# Sheet1.net
KiCad netlist of a schematic drawn in Altium Designer
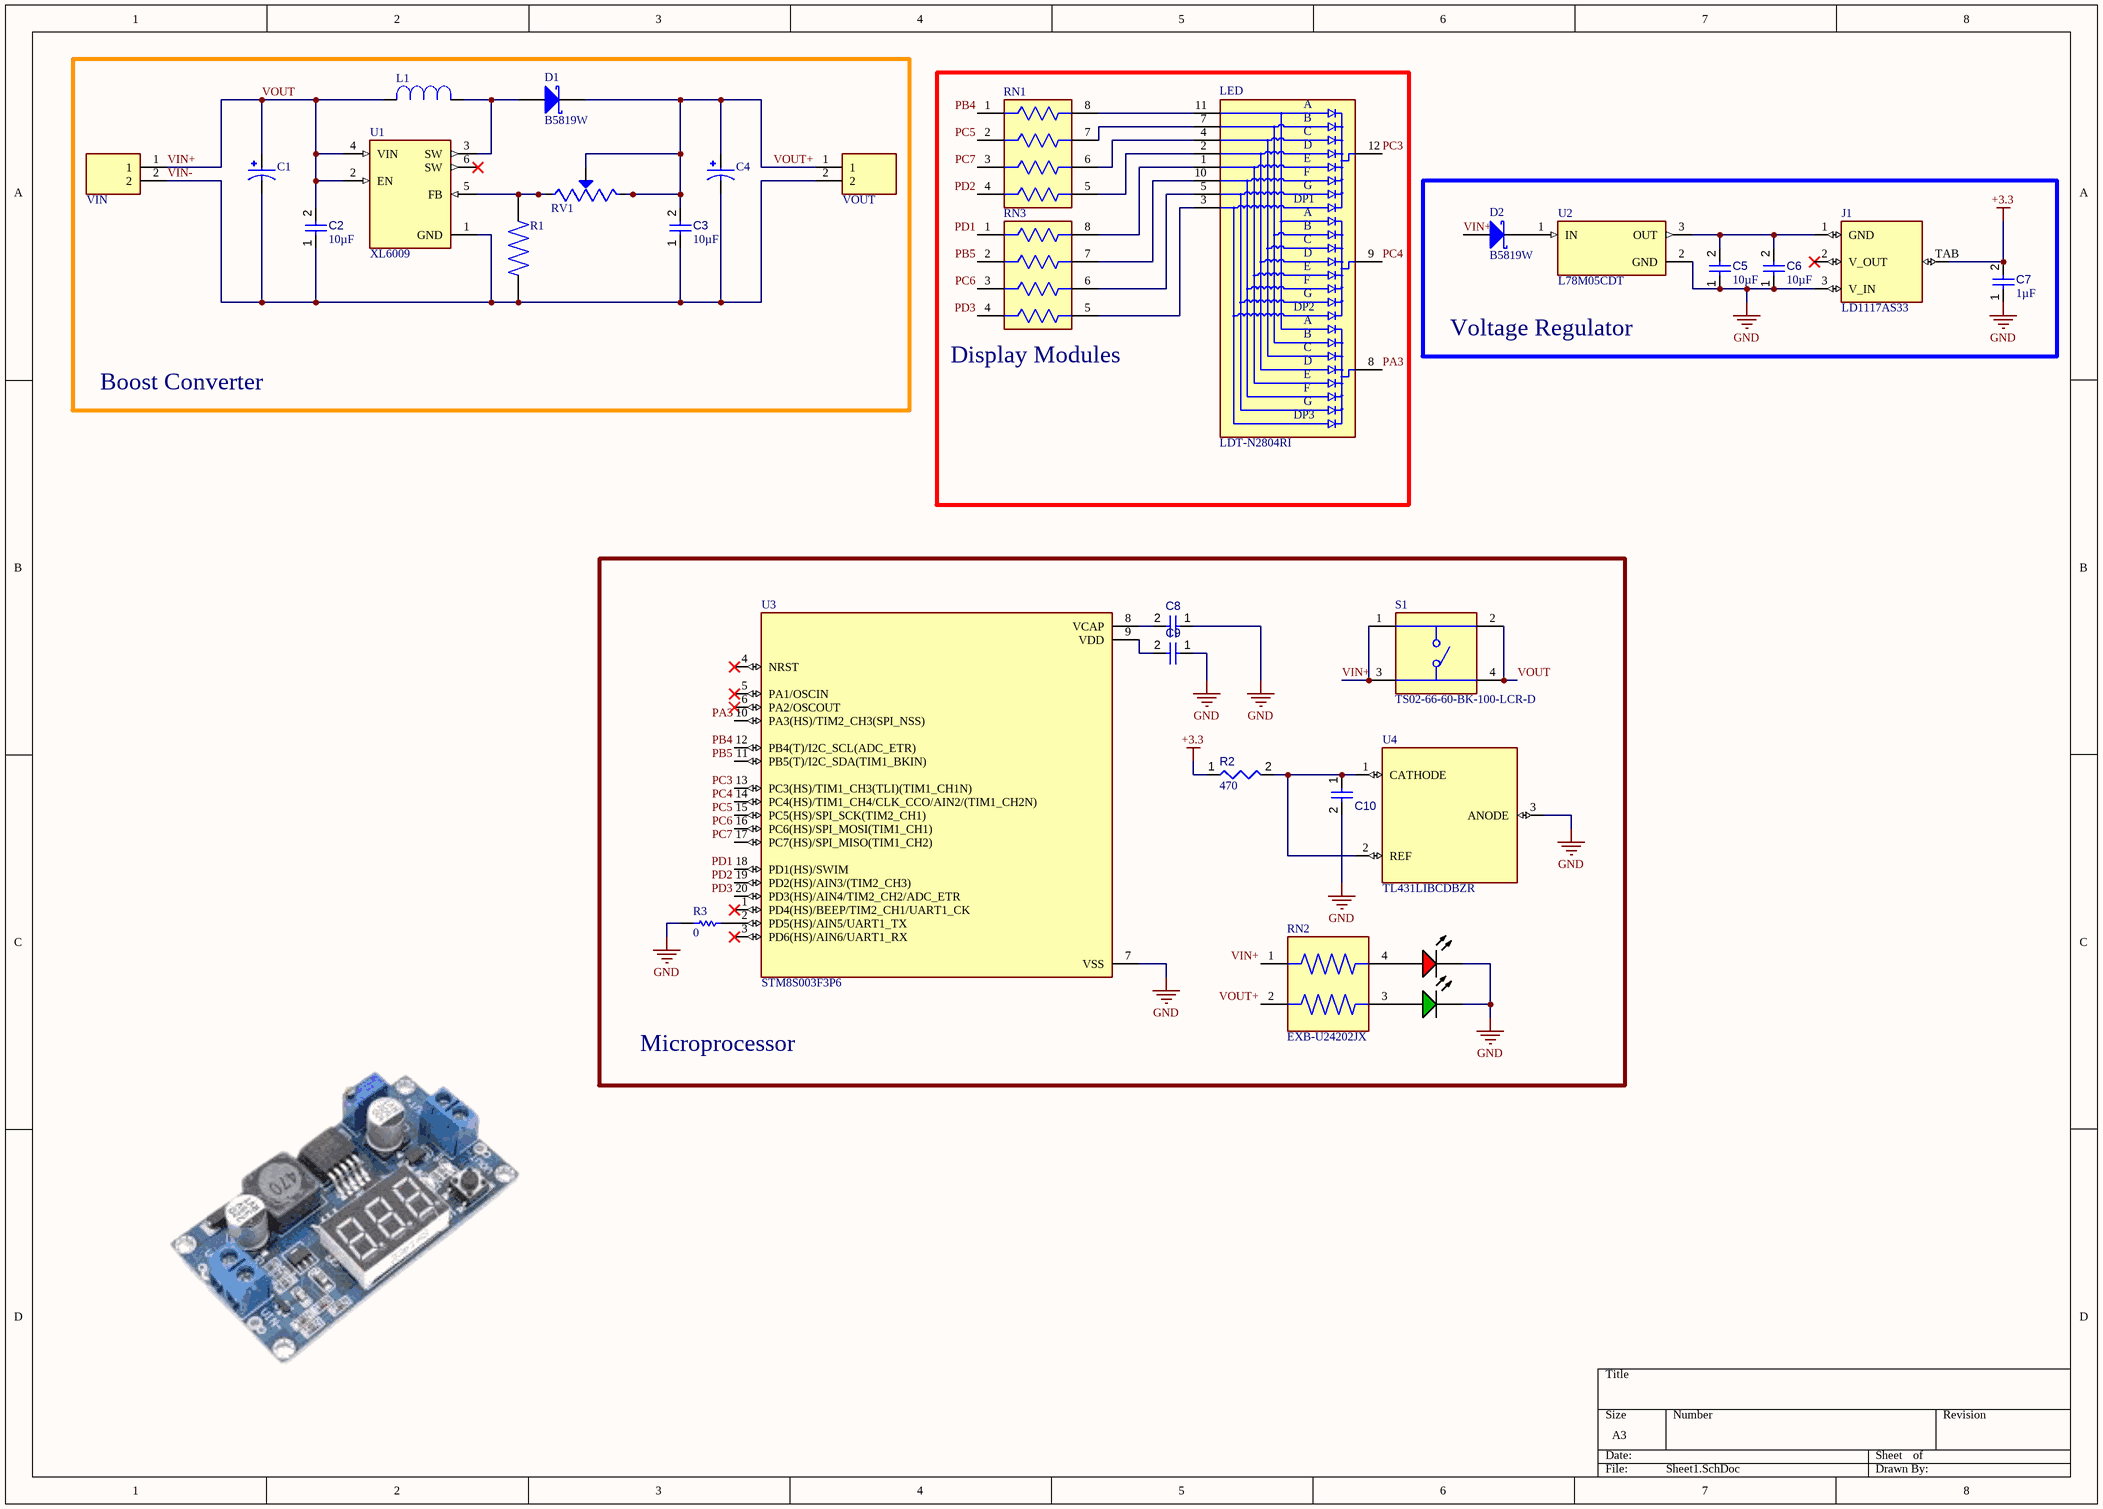
[diagram p0: Sheet1.SchDoc]

(export (version "E")
  (design (tool "Eeschema 10.0.6"))
  (components
    (comp (ref "C1")
      (value "EEEFK1V221P")
      (footprint "CAP_EEEFK1V221P")
      (description "220ÂµF 35V Aluminum Electrolytic Capacitors Radial, Can - SMD 2000 Hrs @ 105Â°C")
      (fields (field (name "MF") "Panasonic"))
      (libsource (lib "220µF 35V Aluminum Electrolytic Capacitors Radial") (part "EEEFK1V221P"))
    )
    (comp (ref "C2")
      (value "10µF")
      (footprint "CAPC0603(1608)100_L")
      (description "Chip Capacitor, 10µF +/-20%, 10V, 0603, Thickness 1 mm")
      (fields (field (name "TOLERANCE") "10%") (field (name "Comment") "Capacitor 10µF +/-20% 10V 0603"))
      (libsource (lib "Med khalil khlifi") (part "CAP-NP-2"))
    )
    (comp (ref "C3")
      (value "10µF")
      (footprint "CAPC0603(1608)100_L")
      (description "Chip Capacitor, 10µF +/-20%, 10V, 0603, Thickness 1 mm")
      (fields (field (name "TOLERANCE") "10%") (field (name "Comment") "Capacitor 10µF +/-20% 10V 0603"))
      (libsource (lib "Med khalil khlifi") (part "CAP-NP-2"))
    )
    (comp (ref "C4")
      (value "EEEFK1V221P")
      (footprint "CAP_EEEFK1V221P")
      (description "220ÂµF 35V Aluminum Electrolytic Capacitors Radial, Can - SMD 2000 Hrs @ 105Â°C")
      (fields (field (name "MF") "Panasonic"))
      (libsource (lib "220µF 35V Aluminum Electrolytic Capacitors Radial") (part "EEEFK1V221P"))
    )
    (comp (ref "C5")
      (value "10µF")
      (footprint "CAPC0603(1608)100_L")
      (description "Chip Capacitor, 10µF +/-20%, 10V, 0603, Thickness 1 mm")
      (fields (field (name "TOLERANCE") "10%") (field (name "Comment") "Capacitor 10µF +/-20% 10V 0603"))
      (libsource (lib "Med khalil khlifi") (part "CAP-NP-2"))
    )
    (comp (ref "C6")
      (value "10µF")
      (footprint "CAPC0603(1608)100_L")
      (description "Chip Capacitor, 10µF +/-20%, 10V, 0603, Thickness 1 mm")
      (fields (field (name "TOLERANCE") "10%") (field (name "Comment") "Capacitor 10µF +/-20% 10V 0603"))
      (libsource (lib "Med khalil khlifi") (part "CAP-NP-2"))
    )
    (comp (ref "C7")
      (value "1µF")
      (footprint "CAPC2013X145X50ML20T25")
      (description "Chip Capacitor, 1 uF, +/-10%, 25 V, 0805 (2012 Metric)")
      (fields (field (name "TOLERANCE") "10%") (field (name "Comment") "Capacitor 1 uF +/- 10% 25 V 0805"))
      (libsource (lib "Med khalil khlifi") (part "CAP-NP-2"))
    )
    (comp (ref "C8")
      (value "Capacitor 10µF +/-20% 10V 0603")
      (footprint "CAPC0603(1608)100_L")
      (description "Chip Capacitor, 10µF +/-20%, 10V, 0603, Thickness 1 mm")
      (fields (field (name "TOLERANCE") "10%"))
      (libsource (lib "Med khalil khlifi") (part "CAP-NP-2"))
    )
    (comp (ref "C9")
      (value "Capacitor 10µF +/-20% 10V 0603")
      (footprint "CAPC0603(1608)100_L")
      (description "Chip Capacitor, 10µF +/-20%, 10V, 0603, Thickness 1 mm")
      (fields (field (name "TOLERANCE") "10%"))
      (libsource (lib "Med khalil khlifi") (part "CAP-NP-2"))
    )
    (comp (ref "C10")
      (value "Capacitor 10µF +/-20% 10V 0603")
      (footprint "CAPC0603(1608)100_L")
      (description "Chip Capacitor, 10µF +/-20%, 10V, 0603, Thickness 1 mm")
      (fields (field (name "TOLERANCE") "10%"))
      (libsource (lib "Med khalil khlifi") (part "CAP-NP-2"))
    )
    (comp (ref "D1")
      (value "B5819W")
      (footprint "MCC-SOD123_V")
      (description "Schottky Barrier Rectifier, 40 V, 1 A, -65 to 125 degC, 2-Pin SOD123, RoHS, Tape and Reel")
      (fields (field (name "MANUFACTURER") "Micro Commercial Components"))
      (libsource (lib "Med khalil khlifi") (part "DSKY-AK-2"))
    )
    (comp (ref "D2")
      (value "B5819W")
      (footprint "MCC-SOD123_V")
      (description "Schottky Barrier Rectifier, 40 V, 1 A, -65 to 125 degC, 2-Pin SOD123, RoHS, Tape and Reel")
      (fields (field (name "MANUFACTURER") "Micro Commercial Components"))
      (libsource (lib "Med khalil khlifi") (part "DSKY-AK-2"))
    )
    (comp (ref "DS2")
      (value "HSMH-C190")
      (footprint "AVAG-HSMX-C190_V")
      (description "LED Uni-Color Red, 65 mW, 20 mA, -40 to 85 degC, 2-Pin SMD, RoHS, Tape and Reel")
      (fields (field (name "POWER") "78mW") (field (name "MANUFACTURER") "Avago"))
      (libsource (lib "Med khalil khlifi") (part "LED-RED-AK-2"))
    )
    (comp (ref "DS3")
      (value "LTST-C190GKT")
      (footprint "LTST-C190GKT_V")
      (description "LED Uni-Color Green, 100 mW, 30 mA, -55 to 85 degC, 2-Pin SMD, RoHS, Tape and Reel")
      (fields (field (name "POWER") "100mW") (field (name "MANUFACTURER") "Lite-On"))
      (libsource (lib "Med khalil khlifi") (part "LED-GREEN-AK-2"))
    )
    (comp (ref "J1")
      (value "LD1117AS33")
      (footprint "SOT223")
      (description "Linear Voltage Regulator IC Positive Fixed 1 Output 1A SOT-223")
      (fields (field (name "MF") "STMicroelectronics"))
      (libsource (lib "LD1117AS33") (part "LD1117AS33"))
    )
    (comp (ref "L1")
      (value "DR125-470-R")
      (footprint "INDM125125X600N")
      (description "47ÂµH Shielded Wirewound Inductor 2.71A 74mOhm Nonstandard")
      (fields (field (name "MF") "Eaton") (field (name "DIGI-KEY_PART_NUMBER") "513-1128-1-ND"))
      (libsource (lib "Inductor-470") (part "DR125-470-R"))
    )
    (comp (ref "LED")
      (value "LDT-N2804RI")
      (footprint "LDT-N2804RI_LUM")
      (fields (field (name "MF") "Lumex Opto/Components"))
      (libsource (lib "Numeric Red 7-Segment 3 Character") (part "LDT-N2804RI"))
    )
    (comp (ref "R1")
      (value "CR0805-FX-3300ELF")
      (footprint "RESC2012X60N")
      (description "330 Ohms Â±1% 0.125W, 1/8W Chip Resistor 0805 _2012 Metric_ Moisture Resistant Thick Film")
      (fields (field (name "MF") "Bourns"))
      (libsource (lib "Res-330Ω") (part "CR0805-FX-3300ELF"))
    )
    (comp (ref "R2")
      (value "470")
      (footprint "RESC0805(2012)_L")
      (description "Chip Resistor, 470 Ohms, +/-5%, 125 mW, -55 to 155 degC, 0805")
      (fields (field (name "TOLERANCE") "5%") (field (name "POWER") "125mW"))
      (libsource (lib "Med khalil khlifi") (part "RES-2"))
    )
    (comp (ref "R3")
      (value "0")
      (footprint "RESC1608X55X25ML10T15")
      (description "Chip Resistor, 0 Ohm, 0.1 W, -55 to 155 degC, 0603 (1608 Metric)")
      (fields (field (name "POWER") "100mW") (field (name "TOLERANCE") "5%"))
      (libsource (lib "") (part "RES-2_1"))
    )
    (comp (ref "RN1")
      (value "CAY16-101J4LF")
      (footprint "FP-CAY16-J4-MFG")
      (description "RES ARRAY 4 RES 100 OHM 1206")
      (fields (field (name "TOLERANCE") "5%"))
      (libsource (lib "resistor array 2") (part "CMP-07230-000011-1"))
    )
    (comp (ref "RN2")
      (value "EXB-U24202JX")
      (footprint "RESCAXE_EXB-U24202JX")
      (fields (field (name "MF") "Panasonic"))
      (libsource (lib "resistor array") (part "EXB-U24202JX"))
    )
    (comp (ref "RN3")
      (value "CAY16-101J4LF")
      (footprint "FP-CAY16-J4-MFG")
      (description "RES ARRAY 4 RES 100 OHM 1206")
      (fields (field (name "TOLERANCE") "5%"))
      (libsource (lib "resistor array 2") (part "CMP-07230-000011-1"))
    )
    (comp (ref "RV1")
      (value "3296W1103LF")
      (footprint "TRIM_3296W1103LF")
      (description "Trimmer, Potentiometer 10kohm 25turn Thd")
      (fields (field (name "MF") "Bourns"))
      (libsource (lib "Potentiometer 1") (part "3296W1103LF"))
    )
    (comp (ref "S1")
      (value "TS02-66-60-BK-100-LCR-D")
      (footprint "SW_TS02-66-60-BK-100-LCR-D")
      (description "6 x 6 mm, 6 mm Actuator Height, 100 gf, Black, Long Crimped, Through Hole, SPST, Tactile Switch")
      (fields (field (name "MF") "Same Sky"))
      (libsource (lib "Push button") (part "TS02-66-60-BK-100-LCR-D"))
    )
    (comp (ref "U1")
      (value "XL6009")
      (footprint "DPAK170P1435X465-6N")
      (fields (field (name "MF") "XLSEMI"))
      (libsource (lib "XL6009") (part "XL6009"))
    )
    (comp (ref "U2")
      (value "L78M05CDT")
      (footprint "VREG_L78M05CDT")
      (fields (field (name "MF") "STMicroelectronics"))
      (libsource (lib "L78M05CDT") (part "L78M05CDT"))
    )
    (comp (ref "U3")
      (value "STM8S003F3P6")
      (footprint "SOP65P640X120-20N")
      (description "STM8 series Microcontroller IC 8-Bit 16MHz 8KB (8K x 8) FLASH 20-TSSOP")
      (fields (field (name "MF") "STMicroelectronics"))
      (libsource (lib "STM8S003F3P6") (part "STM8S003F3P6"))
    )
    (comp (ref "U4")
      (value "TL431LIBCDBZR")
      (footprint "SOT23")
      (description "Adjustable precision shunt regulator with optimized reference current (pin layout: KRA)")
      (fields (field (name "MF") "Texas Instruments"))
      (libsource (lib "TL431LIBCDBZR") (part "TL431LIBCDBZR"))
    )
    (comp (ref "VIN")
      (value "TB006-508-02BE")
      (footprint "CUI_TB006-508-02BE")
      (description "2~24 Poles, Screw Type, Horizontal, 5.08 Pitch, 26~14 (AWG), Terminal Block Connector")
      (fields (field (name "MF") "Same Sky"))
      (libsource (lib "") (part "TB006-508-02BE_1"))
    )
    (comp (ref "VOUT")
      (value "TB006-508-02BE")
      (footprint "CUI_TB006-508-02BE")
      (description "2~24 Poles, Screw Type, Horizontal, 5.08 Pitch, 26~14 (AWG), Terminal Block Connector")
      (fields (field (name "MF") "Same Sky"))
      (libsource (lib "screw terminal block 2") (part "TB006-508-02BE"))
    )
  )
  (nets
    (net (code "1") (name "+3.3") (class "Default")
      (node (ref "C7") (pin "2") (pinfunction "2_2") (pintype "passive"))
      (node (ref "J1") (pin "TAB") (pinfunction "V_OUT2_TAB") (pintype "bidirectional"))
      (node (ref "R2") (pin "1") (pinfunction "1_1") (pintype "passive"))
    )
    (net (code "2") (name "/PA3") (class "Default")
      (node (ref "LED") (pin "8") (pinfunction "8_8") (pintype "passive"))
      (node (ref "U3") (pin "10") (pinfunction "PA3(HS)/TIM2_CH3(SPI_NSS)_10") (pintype "bidirectional"))
    )
    (net (code "3") (name "/PB4") (class "Default")
      (node (ref "RN1") (pin "1") (pinfunction "1_1") (pintype "passive"))
      (node (ref "U3") (pin "12") (pinfunction "PB4(T)/I2C_SCL(ADC_ETR)_12") (pintype "bidirectional"))
    )
    (net (code "4") (name "/PB5") (class "Default")
      (node (ref "RN3") (pin "2") (pinfunction "2_2") (pintype "passive"))
      (node (ref "U3") (pin "11") (pinfunction "PB5(T)/I2C_SDA(TIM1_BKIN)_11") (pintype "bidirectional"))
    )
    (net (code "5") (name "/PC3") (class "Default")
      (node (ref "LED") (pin "12") (pinfunction "12_12") (pintype "passive"))
      (node (ref "U3") (pin "13") (pinfunction "PC3(HS)/TIM1_CH3(TLI)(TIM1_CH1N)_13") (pintype "bidirectional"))
    )
    (net (code "6") (name "/PC4") (class "Default")
      (node (ref "LED") (pin "9") (pinfunction "9_9") (pintype "passive"))
      (node (ref "U3") (pin "14") (pinfunction "PC4(HS)/TIM1_CH4/CLK_CCO/AIN2/(TIM1_CH2N)_14") (pintype "bidirectional"))
    )
    (net (code "7") (name "/PC5") (class "Default")
      (node (ref "RN1") (pin "2") (pinfunction "2_2") (pintype "passive"))
      (node (ref "U3") (pin "15") (pinfunction "PC5(HS)/SPI_SCK(TIM2_CH1)_15") (pintype "bidirectional"))
    )
    (net (code "8") (name "/PC6") (class "Default")
      (node (ref "RN3") (pin "3") (pinfunction "3_3") (pintype "passive"))
      (node (ref "U3") (pin "16") (pinfunction "PC6(HS)/SPI_MOSI(TIM1_CH1)_16") (pintype "bidirectional"))
    )
    (net (code "9") (name "/PC7") (class "Default")
      (node (ref "RN1") (pin "3") (pinfunction "3_3") (pintype "passive"))
      (node (ref "U3") (pin "17") (pinfunction "PC7(HS)/SPI_MISO(TIM1_CH2)_17") (pintype "bidirectional"))
    )
    (net (code "10") (name "/PD1") (class "Default")
      (node (ref "RN3") (pin "1") (pinfunction "1_1") (pintype "passive"))
      (node (ref "U3") (pin "18") (pinfunction "PD1(HS)/SWIM_18") (pintype "bidirectional"))
    )
    (net (code "11") (name "/PD2") (class "Default")
      (node (ref "RN1") (pin "4") (pinfunction "4_4") (pintype "passive"))
      (node (ref "U3") (pin "19") (pinfunction "PD2(HS)/AIN3/(TIM2_CH3)_19") (pintype "bidirectional"))
    )
    (net (code "12") (name "/PD3") (class "Default")
      (node (ref "RN3") (pin "4") (pinfunction "4_4") (pintype "passive"))
      (node (ref "U3") (pin "20") (pinfunction "PD3(HS)/AIN4/TIM2_CH2/ADC_ETR_20") (pintype "bidirectional"))
    )
    (net (code "13") (name "/VIN+") (class "Default")
      (node (ref "C1") (pin "1") (pinfunction "1_1") (pintype "passive"))
      (node (ref "C2") (pin "2") (pinfunction "2_2") (pintype "passive"))
      (node (ref "D2") (pin "1") (pinfunction "A_1") (pintype "passive"))
      (node (ref "L1") (pin "2") (pinfunction "2_2") (pintype "passive"))
      (node (ref "RN2") (pin "1") (pinfunction "1_1") (pintype "passive"))
      (node (ref "S1") (pin "1") (pinfunction "1_1") (pintype "passive"))
      (node (ref "S1") (pin "2") (pinfunction "2_2") (pintype "passive"))
      (node (ref "S1") (pin "3") (pinfunction "3_3") (pintype "passive"))
      (node (ref "S1") (pin "4") (pinfunction "4_4") (pintype "passive"))
      (node (ref "U1") (pin "2") (pinfunction "EN_2") (pintype "input"))
      (node (ref "U1") (pin "4") (pinfunction "VIN_4") (pintype "input"))
      (node (ref "VIN") (pin "1") (pinfunction "1_1") (pintype "passive"))
    )
    (net (code "14") (name "/VIN-") (class "Default")
      (node (ref "C1") (pin "2") (pinfunction "2_2") (pintype "passive"))
      (node (ref "C2") (pin "1") (pinfunction "1_1") (pintype "passive"))
      (node (ref "C3") (pin "1") (pinfunction "1_1") (pintype "passive"))
      (node (ref "C4") (pin "2") (pinfunction "2_2") (pintype "passive"))
      (node (ref "R1") (pin "1") (pinfunction "1_1") (pintype "passive"))
      (node (ref "U1") (pin "1") (pinfunction "GND_1") (pintype "power_in"))
      (node (ref "VIN") (pin "2") (pinfunction "2_2") (pintype "passive"))
      (node (ref "VOUT") (pin "2") (pinfunction "2_2") (pintype "passive"))
    )
    (net (code "15") (name "/VOUT+") (class "Default")
      (node (ref "C3") (pin "2") (pinfunction "2_2") (pintype "passive"))
      (node (ref "C4") (pin "1") (pinfunction "1_1") (pintype "passive"))
      (node (ref "D1") (pin "2") (pinfunction "K_2") (pintype "passive"))
      (node (ref "RN2") (pin "2") (pinfunction "2_2") (pintype "passive"))
      (node (ref "RV1") (pin "2") (pinfunction "WIPER_2") (pintype "passive"))
      (node (ref "RV1") (pin "3") (pinfunction "CW_3") (pintype "passive"))
      (node (ref "VOUT") (pin "1") (pinfunction "1_1") (pintype "passive"))
    )
    (net (code "16") (name "GND") (class "Default")
      (node (ref "C10") (pin "2") (pinfunction "2_2") (pintype "passive"))
      (node (ref "C5") (pin "1") (pinfunction "1_1") (pintype "passive"))
      (node (ref "C6") (pin "1") (pinfunction "1_1") (pintype "passive"))
      (node (ref "C7") (pin "1") (pinfunction "1_1") (pintype "passive"))
      (node (ref "C8") (pin "1") (pinfunction "1_1") (pintype "passive"))
      (node (ref "C9") (pin "1") (pinfunction "1_1") (pintype "passive"))
      (node (ref "DS2") (pin "2") (pinfunction "K_2") (pintype "passive"))
      (node (ref "DS3") (pin "2") (pinfunction "K_2") (pintype "passive"))
      (node (ref "J1") (pin "3") (pinfunction "V_IN_3") (pintype "bidirectional"))
      (node (ref "R3") (pin "1") (pinfunction "1_1") (pintype "passive"))
      (node (ref "U2") (pin "2") (pinfunction "GND_2") (pintype "power_in"))
      (node (ref "U3") (pin "7") (pinfunction "VSS_7") (pintype "power_in"))
      (node (ref "U4") (pin "3") (pinfunction "ANODE_3") (pintype "bidirectional"))
    )
    (net (code "17") (name "Net-(D1-A)") (class "Default")
      (node (ref "D1") (pin "1") (pinfunction "A_1") (pintype "passive"))
      (node (ref "L1") (pin "1") (pinfunction "1_1") (pintype "passive"))
      (node (ref "U1") (pin "3") (pinfunction "SW_3") (pintype "output"))
    )
    (net (code "18") (name "Net-(D2-K)") (class "Default")
      (node (ref "D2") (pin "2") (pinfunction "K_2") (pintype "passive"))
      (node (ref "U2") (pin "1") (pinfunction "IN_1") (pintype "input"))
    )
    (net (code "19") (name "Net-(DS2-A)") (class "Default")
      (node (ref "DS2") (pin "1") (pinfunction "A_1") (pintype "passive"))
      (node (ref "RN2") (pin "4") (pinfunction "4_4") (pintype "passive"))
    )
    (net (code "20") (name "Net-(DS3-A)") (class "Default")
      (node (ref "DS3") (pin "1") (pinfunction "A_1") (pintype "passive"))
      (node (ref "RN2") (pin "3") (pinfunction "3_3") (pintype "passive"))
    )
    (net (code "21") (name "Net-(J1-GND)") (class "Default")
      (node (ref "C5") (pin "2") (pinfunction "2_2") (pintype "passive"))
      (node (ref "C6") (pin "2") (pinfunction "2_2") (pintype "passive"))
      (node (ref "J1") (pin "1") (pinfunction "GND_1") (pintype "bidirectional"))
      (node (ref "U2") (pin "3") (pinfunction "OUT_3") (pintype "output"))
    )
    (net (code "22") (name "Net-(LED-Pad1)") (class "Default")
      (node (ref "LED") (pin "1") (pinfunction "1_1") (pintype "passive"))
      (node (ref "RN3") (pin "8") (pinfunction "8_8") (pintype "passive"))
    )
    (net (code "23") (name "Net-(LED-Pad2)") (class "Default")
      (node (ref "LED") (pin "2") (pinfunction "2_2") (pintype "passive"))
      (node (ref "RN1") (pin "5") (pinfunction "5_5") (pintype "passive"))
    )
    (net (code "24") (name "Net-(LED-Pad3)") (class "Default")
      (node (ref "LED") (pin "3") (pinfunction "3_3") (pintype "passive"))
      (node (ref "RN3") (pin "5") (pinfunction "5_5") (pintype "passive"))
    )
    (net (code "25") (name "Net-(LED-Pad4)") (class "Default")
      (node (ref "LED") (pin "4") (pinfunction "4_4") (pintype "passive"))
      (node (ref "RN1") (pin "6") (pinfunction "6_6") (pintype "passive"))
    )
    (net (code "26") (name "Net-(LED-Pad5)") (class "Default")
      (node (ref "LED") (pin "5") (pinfunction "5_5") (pintype "passive"))
      (node (ref "RN3") (pin "6") (pinfunction "6_6") (pintype "passive"))
    )
    (net (code "27") (name "Net-(LED-Pad7)") (class "Default")
      (node (ref "LED") (pin "7") (pinfunction "7_7") (pintype "passive"))
      (node (ref "RN1") (pin "7") (pinfunction "7_7") (pintype "passive"))
    )
    (net (code "28") (name "Net-(LED-Pad10)") (class "Default")
      (node (ref "LED") (pin "10") (pinfunction "10_10") (pintype "passive"))
      (node (ref "RN3") (pin "7") (pinfunction "7_7") (pintype "passive"))
    )
    (net (code "29") (name "Net-(LED-Pad11)") (class "Default")
      (node (ref "LED") (pin "11") (pinfunction "11_11") (pintype "passive"))
      (node (ref "RN1") (pin "8") (pinfunction "8_8") (pintype "passive"))
    )
    (net (code "30") (name "Net-(RV1-CCW)") (class "Default")
      (node (ref "R1") (pin "2") (pinfunction "2_2") (pintype "passive"))
      (node (ref "RV1") (pin "1") (pinfunction "CCW_1") (pintype "passive"))
      (node (ref "U1") (pin "5") (pinfunction "FB_5") (pintype "input"))
    )
    (net (code "31") (name "Net-(U3-PD5(HS){slash}AIN5{slash}UART1_TX)") (class "Default")
      (node (ref "R3") (pin "2") (pinfunction "2_2") (pintype "passive"))
      (node (ref "U3") (pin "2") (pinfunction "PD5(HS)/AIN5/UART1_TX_2") (pintype "bidirectional"))
    )
    (net (code "32") (name "Net-(U3-VCAP)") (class "Default")
      (node (ref "C8") (pin "2") (pinfunction "2_2") (pintype "passive"))
      (node (ref "U3") (pin "8") (pinfunction "VCAP_8") (pintype "power_in"))
    )
    (net (code "33") (name "Net-(U3-VDD)") (class "Default")
      (node (ref "C9") (pin "2") (pinfunction "2_2") (pintype "passive"))
      (node (ref "U3") (pin "9") (pinfunction "VDD_9") (pintype "power_in"))
    )
    (net (code "34") (name "Net-(U4-CATHODE)") (class "Default")
      (node (ref "C10") (pin "1") (pinfunction "1_1") (pintype "passive"))
      (node (ref "R2") (pin "2") (pinfunction "2_2") (pintype "passive"))
      (node (ref "U4") (pin "1") (pinfunction "CATHODE_1") (pintype "bidirectional"))
      (node (ref "U4") (pin "2") (pinfunction "REF_2") (pintype "bidirectional"))
    )
    (net (code "35") (name "unconnected-(J1-V_OUT-Pad2)") (class "Default")
      (node (ref "J1") (pin "2") (pinfunction "V_OUT_2") (pintype "bidirectional+no_connect"))
    )
    (net (code "36") (name "unconnected-(U1-SW-Pad6)") (class "Default")
      (node (ref "U1") (pin "6") (pinfunction "SW_6") (pintype "output+no_connect"))
    )
    (net (code "37") (name "unconnected-(U3-NRST-Pad4)") (class "Default")
      (node (ref "U3") (pin "4") (pinfunction "NRST_4") (pintype "bidirectional+no_connect"))
    )
    (net (code "38") (name "unconnected-(U3-PA1{slash}OSCIN-Pad5)") (class "Default")
      (node (ref "U3") (pin "5") (pinfunction "PA1/OSCIN_5") (pintype "bidirectional+no_connect"))
    )
    (net (code "39") (name "unconnected-(U3-PA2{slash}OSCOUT-Pad6)") (class "Default")
      (node (ref "U3") (pin "6") (pinfunction "PA2/OSCOUT_6") (pintype "bidirectional+no_connect"))
    )
    (net (code "40") (name "unconnected-(U3-PD4(HS){slash}BEEP{slash}TIM2_CH1{slash}UART1_CK-Pad1)") (class "Default")
      (node (ref "U3") (pin "1") (pinfunction "PD4(HS)/BEEP/TIM2_CH1/UART1_CK_1") (pintype "bidirectional+no_connect"))
    )
    (net (code "41") (name "unconnected-(U3-PD6(HS){slash}AIN6{slash}UART1_RX-Pad3)") (class "Default")
      (node (ref "U3") (pin "3") (pinfunction "PD6(HS)/AIN6/UART1_RX_3") (pintype "bidirectional+no_connect"))
    )
  )
)
